# ProPrj_DevBoard_2026-04-14.net
KiCad netlist of a schematic drawn in EasyEDA Pro
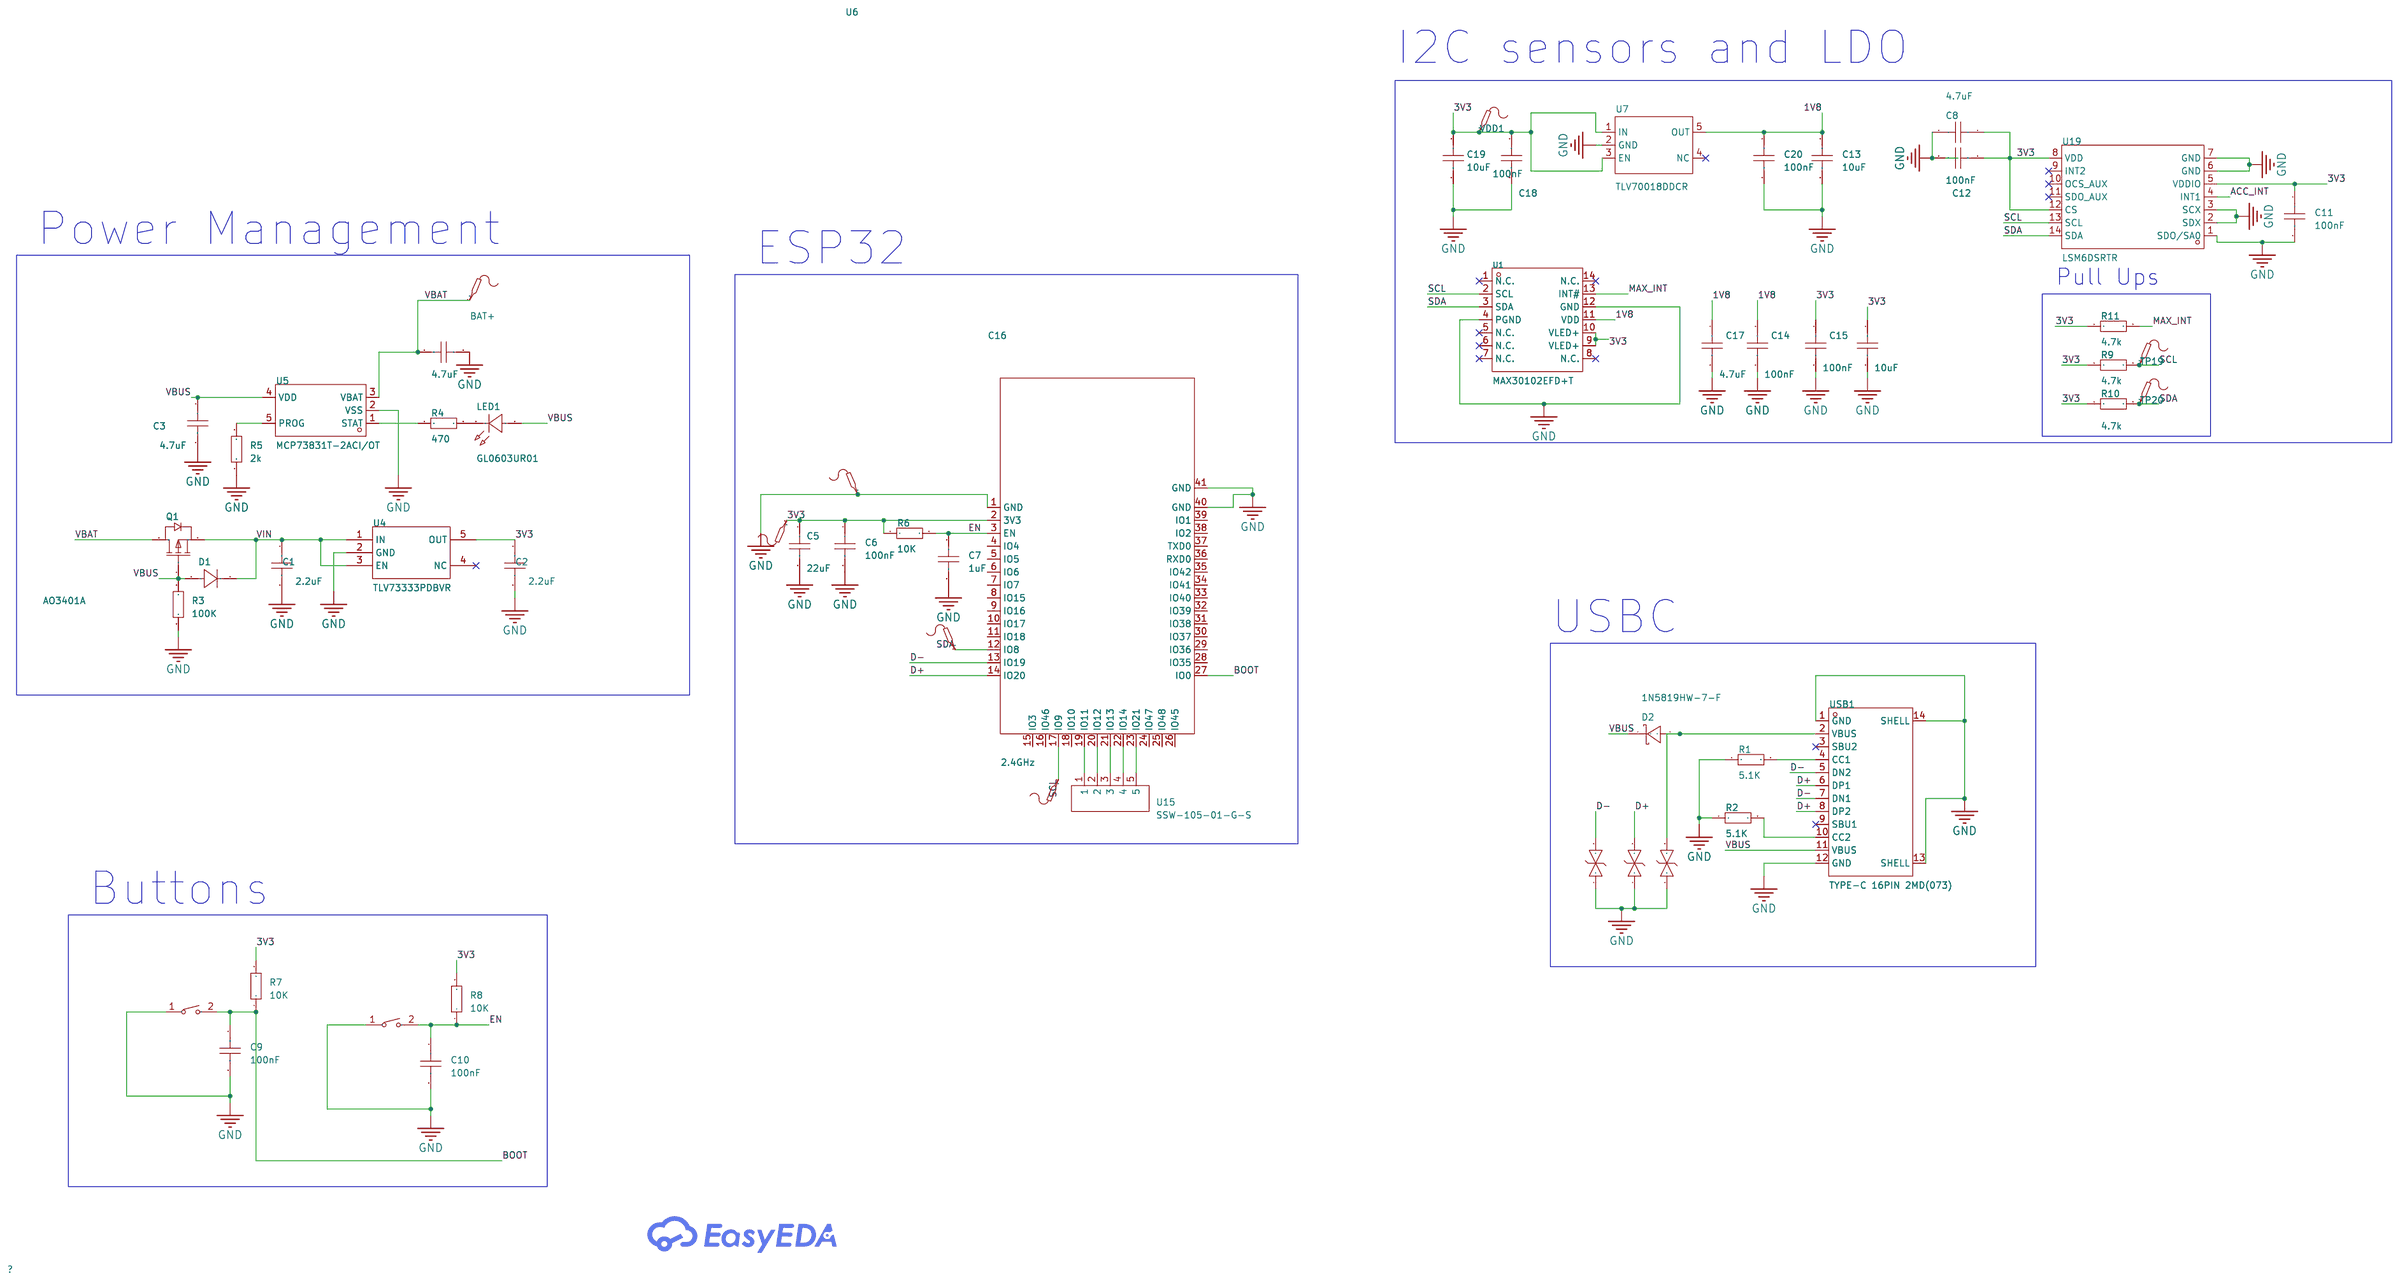
[diagram p0: schematic sheet]

(export (version "E")
  (design (tool "Eeschema 10.0.6"))
  (components
    (comp (ref "BAT+")
      (value "~")
      (footprint "easyedapro:Test-Point-0.5mm")
      (description "Test Point 测试点")
      (libsource (lib "easyedapro") (part "Test-Point"))
    )
    (comp (ref "BAT+1")
      (value "~")
      (footprint "easyedapro:Test-Point-0.5mm")
      (description "Test Point 测试点")
      (libsource (lib "easyedapro") (part "Test-Point"))
    )
    (comp (ref "BAT+2")
      (value "~")
      (footprint "easyedapro:Test-Point-0.5mm")
      (description "Test Point 测试点")
      (libsource (lib "easyedapro") (part "Test-Point"))
    )
    (comp (ref "BAT+3")
      (value "~")
      (footprint "easyedapro:Test-Point-0.5mm")
      (description "Test Point 测试点")
      (libsource (lib "easyedapro") (part "Test-Point"))
    )
    (comp (ref "BAT+4")
      (value "~")
      (footprint "easyedapro:Test-Point-0.5mm")
      (description "Test Point 测试点")
      (libsource (lib "easyedapro") (part "Test-Point"))
    )
    (comp (ref "C1")
      (value "2.2uF")
      (footprint "easyedapro:C0603")
      (libsource (lib "easyedapro") (part "CAP"))
    )
    (comp (ref "C2")
      (value "2.2uF")
      (footprint "easyedapro:C0603")
      (libsource (lib "easyedapro") (part "CAP"))
    )
    (comp (ref "C3")
      (value "4.7uF")
      (footprint "easyedapro:C0603")
      (libsource (lib "easyedapro") (part "CAP"))
    )
    (comp (ref "C4")
      (value "4.7uF")
      (footprint "easyedapro:C0603")
      (libsource (lib "easyedapro") (part "CAP"))
    )
    (comp (ref "C5")
      (value "22uF")
      (footprint "easyedapro:C0603")
      (libsource (lib "easyedapro") (part "CAP"))
    )
    (comp (ref "C6")
      (value "100nF")
      (footprint "easyedapro:C0603")
      (libsource (lib "easyedapro") (part "CAP"))
    )
    (comp (ref "C7") (value "1uF") (footprint "easyedapro:C0603") (libsource (lib "easyedapro") (part "CAP")))
    (comp (ref "C8")
      (value "4.7uF")
      (footprint "easyedapro:C0603")
      (libsource (lib "easyedapro") (part "CAP"))
    )
    (comp (ref "C9")
      (value "100nF")
      (footprint "easyedapro:C0603")
      (libsource (lib "easyedapro") (part "CAP"))
    )
    (comp (ref "C10")
      (value "100nF")
      (footprint "easyedapro:C0603")
      (libsource (lib "easyedapro") (part "CAP"))
    )
    (comp (ref "C11")
      (value "100nF")
      (footprint "easyedapro:C0603")
      (libsource (lib "easyedapro") (part "CAP"))
    )
    (comp (ref "C12")
      (value "100nF")
      (footprint "easyedapro:C0603")
      (libsource (lib "easyedapro") (part "CAP"))
    )
    (comp (ref "C13")
      (value "10uF")
      (footprint "easyedapro:C0603")
      (libsource (lib "easyedapro") (part "CAP"))
    )
    (comp (ref "C14")
      (value "100nF")
      (footprint "easyedapro:C0603")
      (libsource (lib "easyedapro") (part "CAP"))
    )
    (comp (ref "C15")
      (value "100nF")
      (footprint "easyedapro:C0603")
      (libsource (lib "easyedapro") (part "CAP"))
    )
    (comp (ref "C16")
      (value "10uF")
      (footprint "easyedapro:C0603")
      (libsource (lib "easyedapro") (part "CAP"))
    )
    (comp (ref "C17")
      (value "4.7uF")
      (footprint "easyedapro:C0603")
      (libsource (lib "easyedapro") (part "CAP"))
    )
    (comp (ref "C18")
      (value "100nF")
      (footprint "easyedapro:C0603")
      (libsource (lib "easyedapro") (part "CAP"))
    )
    (comp (ref "C19")
      (value "10uF")
      (footprint "easyedapro:C0603")
      (libsource (lib "easyedapro") (part "CAP"))
    )
    (comp (ref "C20")
      (value "100nF")
      (footprint "easyedapro:C0603")
      (libsource (lib "easyedapro") (part "CAP"))
    )
    (comp (ref "D1")
      (value "~")
      (footprint "easyedapro:SMA_L4.4-W2.8-LS5.4-RD")
      (libsource (lib "easyedapro") (part "D_1N4007"))
    )
    (comp (ref "D2")
      (value "1N5819HW-7-F")
      (footprint "easyedapro:SOD-123_L2.7-W1.6-LS3.7-RD")
      (fields (field (name "Manufacturer") "DIODES(美台)"))
      (libsource (lib "easyedapro") (part "1N5819HW-7-F"))
    )
    (comp (ref "LED1")
      (value "GL0603UR01")
      (footprint "easyedapro:LED0603-FD")
      (fields (field (name "Manufacturer") "Guiguang light(桂光光电)"))
      (libsource (lib "easyedapro") (part "GL0603UR01"))
    )
    (comp (ref "Q1")
      (value "AO3401A")
      (footprint "easyedapro:SOT-23_L2.9-W1.3-P1.90-LS2.4-BR")
      (fields (field (name "Manufacturer") "AOS"))
      (libsource (lib "easyedapro") (part "AO3401A"))
    )
    (comp (ref "R1")
      (value "5.1K")
      (footprint "easyedapro:R0603")
      (libsource (lib "easyedapro") (part "Res"))
    )
    (comp (ref "R2")
      (value "5.1K")
      (footprint "easyedapro:R0603")
      (libsource (lib "easyedapro") (part "Res"))
    )
    (comp (ref "R3")
      (value "100K")
      (footprint "easyedapro:R0603")
      (libsource (lib "easyedapro") (part "Res"))
    )
    (comp (ref "R4") (value "470") (footprint "easyedapro:R0603") (libsource (lib "easyedapro") (part "Res")))
    (comp (ref "R5") (value "2k") (footprint "easyedapro:R0603") (libsource (lib "easyedapro") (part "Res")))
    (comp (ref "R6") (value "10K") (footprint "easyedapro:R0603") (libsource (lib "easyedapro") (part "Res")))
    (comp (ref "R7") (value "10K") (footprint "easyedapro:R0603") (libsource (lib "easyedapro") (part "Res")))
    (comp (ref "R8") (value "10K") (footprint "easyedapro:R0603") (libsource (lib "easyedapro") (part "Res")))
    (comp (ref "R9")
      (value "4.7k")
      (footprint "easyedapro:R0603")
      (libsource (lib "easyedapro") (part "Res"))
    )
    (comp (ref "R10")
      (value "4.7k")
      (footprint "easyedapro:R0603")
      (libsource (lib "easyedapro") (part "Res"))
    )
    (comp (ref "R11")
      (value "4.7k")
      (footprint "easyedapro:R0603")
      (libsource (lib "easyedapro") (part "Res"))
    )
    (comp (ref "TP19")
      (value "~")
      (footprint "easyedapro:Test-Point-0.5mm")
      (description "Test Point 测试点")
      (libsource (lib "easyedapro") (part "Test-Point"))
    )
    (comp (ref "TP20")
      (value "~")
      (footprint "easyedapro:Test-Point-0.5mm")
      (description "Test Point 测试点")
      (libsource (lib "easyedapro") (part "Test-Point"))
    )
    (comp (ref "U1")
      (value "MAX30102EFD+T")
      (footprint "easyedapro:OESIP-14_L5.6-W3.3-P0.80-TL")
      (description "Operating Temperature:-40°C~+85°C Operating Temperature:-40°C~+85°C")
      (fields (field (name "Manufacturer") "ADI(亚德诺)/MAXIM(美信)"))
      (libsource (lib "easyedapro") (part "MAX30102EFD+T_C6454833"))
    )
    (comp (ref "U4")
      (value "TLV73333PDBVR")
      (footprint "easyedapro:SOT-23-5_L3.0-W1.7-P0.95-LS2.8-BR")
      (fields (field (name "Manufacturer") "TI(德州仪器)"))
      (libsource (lib "easyedapro") (part "TLV73333PDBVR"))
    )
    (comp (ref "U5")
      (value "MCP73831T-2ACI/OT")
      (footprint "easyedapro:SOT-23-5_L3.0-W1.7-P0.95-LS2.8-BL")
      (fields (field (name "Manufacturer") "MICROCHIP(美国微芯)"))
      (libsource (lib "easyedapro") (part "MCP73831T-2ACI/OT"))
    )
    (comp (ref "U6")
      (value "2.4GHz")
      (footprint "easyedapro:WIRELM-SMD_ESP32-S3-WROOM-1")
      (fields
        (field (name "Manufacturer Part") "ESP32-S3-WROOM-1-N16R8")
        (field (name "Manufacturer") "ESPRESSIF(乐鑫)")
      )
      (libsource (lib "easyedapro") (part "ESP32-S3-WROOM-1(N16R8)"))
    )
    (comp (ref "U7")
      (value "TLV70018DDCR")
      (footprint "easyedapro:SOT-23-5_L3.0-W1.7-P0.95-LS2.8-BR")
      (fields (field (name "Manufacturer") "TI(德州仪器)"))
      (libsource (lib "easyedapro") (part "TLV70018DDCR"))
    )
    (comp (ref "U8")
      (value "GT-TC060A-H025-L1")
      (footprint "easyedapro:SW-SMD_L6.1-W3.5-LS8.0")
      (fields (field (name "Manufacturer") "G-Switch(品赞)"))
      (libsource (lib "easyedapro") (part "GT-TC060A-H025-L1"))
    )
    (comp (ref "U9")
      (value "GT-TC060A-H025-L1")
      (footprint "easyedapro:SW-SMD_L6.1-W3.5-LS8.0")
      (fields (field (name "Manufacturer") "G-Switch(品赞)"))
      (libsource (lib "easyedapro") (part "GT-TC060A-H025-L1"))
    )
    (comp (ref "U15")
      (value "SSW-105-01-G-S")
      (footprint "easyedapro:HDR-TH_5P-P2.54_SSW-105-01-S-P")
      (fields (field (name "Manufacturer") "SAMTEC"))
      (libsource (lib "easyedapro") (part "SSW-105-01-G-S"))
    )
    (comp (ref "U16")
      (value "LESD5D5.0CT1G")
      (footprint "easyedapro:SOD-523_L1.2-W0.8-LS1.6-BI")
      (fields (field (name "Manufacturer") "KUU"))
      (libsource (lib "easyedapro") (part "LESD5D5.0CT1G_C7433850"))
    )
    (comp (ref "U17")
      (value "LESD5D5.0CT1G")
      (footprint "easyedapro:SOD-523_L1.2-W0.8-LS1.6-BI")
      (fields (field (name "Manufacturer") "KUU"))
      (libsource (lib "easyedapro") (part "LESD5D5.0CT1G_C7433850"))
    )
    (comp (ref "U18")
      (value "LESD5D5.0CT1G")
      (footprint "easyedapro:SOD-523_L1.2-W0.8-LS1.6-BI")
      (fields (field (name "Manufacturer") "KUU"))
      (libsource (lib "easyedapro") (part "LESD5D5.0CT1G_C7433850"))
    )
    (comp (ref "U19")
      (value "LSM6DSRTR")
      (footprint "easyedapro:LGA-14_L3.0-W2.5-P0.50-BR")
      (fields (field (name "Manufacturer") "ST(意法半导体)"))
      (libsource (lib "easyedapro") (part "LSM6DSRTR"))
    )
    (comp (ref "USB1")
      (value "TYPE-C 16PIN 2MD(073)")
      (footprint "easyedapro:USB-C-SMD_TYPE-C-6PIN-2MD-073")
      (fields (field (name "Manufacturer") "SHOU HAN(首韩)"))
      (libsource (lib "easyedapro") (part "TYPE-C 16PIN 2MD(073)"))
    )
    (comp (ref "VDD1")
      (value "~")
      (footprint "easyedapro:Test-Point-0.5mm")
      (description "Test Point 测试点")
      (libsource (lib "easyedapro") (part "Test-Point"))
    )
  )
  (nets
    (net (code "1") (name "/1V8") (class "Default")
      (node (ref "C13") (pin "1") (pinfunction "1_1") (pintype "input"))
      (node (ref "C14") (pin "1") (pinfunction "1_1") (pintype "input"))
      (node (ref "C17") (pin "1") (pinfunction "1_1") (pintype "input"))
      (node (ref "C20") (pin "1") (pinfunction "1_1") (pintype "input"))
      (node (ref "U1") (pin "11") (pinfunction "VDD_11") (pintype "input"))
      (node (ref "U7") (pin "5") (pinfunction "OUT_5") (pintype "unspecified"))
    )
    (net (code "2") (name "/3V3") (class "Default")
      (node (ref "BAT+3") (pin "1") (pinfunction "1_1") (pintype "unspecified"))
      (node (ref "C11") (pin "1") (pinfunction "1_1") (pintype "input"))
      (node (ref "C12") (pin "1") (pinfunction "1_1") (pintype "input"))
      (node (ref "C15") (pin "1") (pinfunction "1_1") (pintype "input"))
      (node (ref "C16") (pin "1") (pinfunction "1_1") (pintype "input"))
      (node (ref "C18") (pin "1") (pinfunction "1_1") (pintype "input"))
      (node (ref "C19") (pin "1") (pinfunction "1_1") (pintype "input"))
      (node (ref "C2") (pin "1") (pinfunction "1_1") (pintype "input"))
      (node (ref "C5") (pin "1") (pinfunction "1_1") (pintype "input"))
      (node (ref "C6") (pin "1") (pinfunction "1_1") (pintype "input"))
      (node (ref "C8") (pin "1") (pinfunction "1_1") (pintype "input"))
      (node (ref "R10") (pin "1") (pinfunction "1_1") (pintype "input"))
      (node (ref "R11") (pin "1") (pinfunction "1_1") (pintype "input"))
      (node (ref "R6") (pin "1") (pinfunction "1_1") (pintype "input"))
      (node (ref "R7") (pin "2") (pinfunction "2_2") (pintype "input"))
      (node (ref "R8") (pin "2") (pinfunction "2_2") (pintype "input"))
      (node (ref "R9") (pin "1") (pinfunction "1_1") (pintype "input"))
      (node (ref "U1") (pin "10") (pinfunction "VLED+_10") (pintype "input"))
      (node (ref "U1") (pin "9") (pinfunction "VLED+_9") (pintype "input"))
      (node (ref "U19") (pin "12") (pinfunction "CS_12") (pintype "unspecified"))
      (node (ref "U19") (pin "5") (pinfunction "VDDIO_5") (pintype "unspecified"))
      (node (ref "U19") (pin "8") (pinfunction "VDD_8") (pintype "unspecified"))
      (node (ref "U4") (pin "5") (pinfunction "OUT_5") (pintype "unspecified"))
      (node (ref "U6") (pin "2") (pinfunction "3V3_2") (pintype "unspecified"))
      (node (ref "U7") (pin "1") (pinfunction "IN_1") (pintype "unspecified"))
      (node (ref "U7") (pin "3") (pinfunction "EN_3") (pintype "unspecified"))
      (node (ref "VDD1") (pin "1") (pinfunction "1_1") (pintype "unspecified"))
    )
    (net (code "3") (name "/ACC_INT") (class "Default")
      (node (ref "U19") (pin "4") (pinfunction "INT1_4") (pintype "unspecified"))
    )
    (net (code "4") (name "/BOOT") (class "Default")
      (node (ref "C9") (pin "1") (pinfunction "1_1") (pintype "input"))
      (node (ref "R7") (pin "1") (pinfunction "1_1") (pintype "input"))
      (node (ref "U6") (pin "27") (pinfunction "IO0_27") (pintype "unspecified"))
      (node (ref "U8") (pin "2") (pinfunction "2_2") (pintype "unspecified"))
    )
    (net (code "5") (name "/D+") (class "Default")
      (node (ref "U17") (pin "2") (pinfunction "2_2") (pintype "unspecified"))
      (node (ref "U6") (pin "14") (pinfunction "IO20_14") (pintype "unspecified"))
      (node (ref "USB1") (pin "6") (pinfunction "DP1_6") (pintype "unspecified"))
      (node (ref "USB1") (pin "8") (pinfunction "DP2_8") (pintype "unspecified"))
    )
    (net (code "6") (name "/D-") (class "Default")
      (node (ref "U16") (pin "2") (pinfunction "2_2") (pintype "unspecified"))
      (node (ref "U6") (pin "13") (pinfunction "IO19_13") (pintype "unspecified"))
      (node (ref "USB1") (pin "5") (pinfunction "DN2_5") (pintype "unspecified"))
      (node (ref "USB1") (pin "7") (pinfunction "DN1_7") (pintype "unspecified"))
    )
    (net (code "7") (name "/EN") (class "Default")
      (node (ref "C10") (pin "1") (pinfunction "1_1") (pintype "input"))
      (node (ref "C7") (pin "1") (pinfunction "1_1") (pintype "input"))
      (node (ref "R6") (pin "2") (pinfunction "2_2") (pintype "input"))
      (node (ref "R8") (pin "1") (pinfunction "1_1") (pintype "input"))
      (node (ref "U6") (pin "3") (pinfunction "EN_3") (pintype "unspecified"))
      (node (ref "U9") (pin "2") (pinfunction "2_2") (pintype "unspecified"))
    )
    (net (code "8") (name "/MAX_INT") (class "Default")
      (node (ref "R11") (pin "2") (pinfunction "2_2") (pintype "input"))
      (node (ref "U1") (pin "13") (pinfunction "INT#_13") (pintype "input"))
    )
    (net (code "9") (name "/SCL") (class "Default")
      (node (ref "BAT+1") (pin "1") (pinfunction "1_1") (pintype "unspecified"))
      (node (ref "R9") (pin "2") (pinfunction "2_2") (pintype "input"))
      (node (ref "TP19") (pin "1") (pinfunction "1_1") (pintype "unspecified"))
      (node (ref "U1") (pin "2") (pinfunction "SCL_2") (pintype "input"))
      (node (ref "U19") (pin "13") (pinfunction "SCL_13") (pintype "unspecified"))
      (node (ref "U6") (pin "17") (pinfunction "IO9_17") (pintype "unspecified"))
    )
    (net (code "10") (name "/SDA") (class "Default")
      (node (ref "BAT+2") (pin "1") (pinfunction "1_1") (pintype "unspecified"))
      (node (ref "R10") (pin "2") (pinfunction "2_2") (pintype "input"))
      (node (ref "TP20") (pin "1") (pinfunction "1_1") (pintype "unspecified"))
      (node (ref "U1") (pin "3") (pinfunction "SDA_3") (pintype "input"))
      (node (ref "U19") (pin "14") (pinfunction "SDA_14") (pintype "unspecified"))
      (node (ref "U6") (pin "12") (pinfunction "IO8_12") (pintype "unspecified"))
    )
    (net (code "11") (name "/VBAT") (class "Default")
      (node (ref "BAT+") (pin "1") (pinfunction "1_1") (pintype "unspecified"))
      (node (ref "C4") (pin "1") (pinfunction "1_1") (pintype "input"))
      (node (ref "Q1") (pin "3") (pinfunction "D_3") (pintype "unspecified"))
      (node (ref "U5") (pin "3") (pinfunction "VBAT_3") (pintype "unspecified"))
    )
    (net (code "12") (name "/VBUS") (class "Default")
      (node (ref "C3") (pin "1") (pinfunction "1_1") (pintype "input"))
      (node (ref "D1") (pin "2") (pinfunction "A_2") (pintype "input"))
      (node (ref "D2") (pin "1") (pinfunction "K_1") (pintype "unspecified"))
      (node (ref "LED1") (pin "1") (pinfunction "A_1") (pintype "unspecified"))
      (node (ref "Q1") (pin "1") (pinfunction "G_1") (pintype "unspecified"))
      (node (ref "R3") (pin "2") (pinfunction "2_2") (pintype "input"))
      (node (ref "U5") (pin "4") (pinfunction "VDD_4") (pintype "unspecified"))
      (node (ref "USB1") (pin "11") (pinfunction "VBUS_11") (pintype "unspecified"))
    )
    (net (code "13") (name "/VIN") (class "Default")
      (node (ref "C1") (pin "1") (pinfunction "1_1") (pintype "input"))
      (node (ref "D1") (pin "1") (pinfunction "K_1") (pintype "input"))
      (node (ref "Q1") (pin "2") (pinfunction "S_2") (pintype "unspecified"))
      (node (ref "U4") (pin "1") (pinfunction "IN_1") (pintype "unspecified"))
      (node (ref "U4") (pin "3") (pinfunction "EN_3") (pintype "unspecified"))
    )
    (net (code "14") (name "GND") (class "Default")
      (node (ref "BAT+4") (pin "1") (pinfunction "1_1") (pintype "unspecified"))
      (node (ref "C1") (pin "2") (pinfunction "2_2") (pintype "input"))
      (node (ref "C10") (pin "2") (pinfunction "2_2") (pintype "input"))
      (node (ref "C11") (pin "2") (pinfunction "2_2") (pintype "input"))
      (node (ref "C12") (pin "2") (pinfunction "2_2") (pintype "input"))
      (node (ref "C13") (pin "2") (pinfunction "2_2") (pintype "input"))
      (node (ref "C14") (pin "2") (pinfunction "2_2") (pintype "input"))
      (node (ref "C15") (pin "2") (pinfunction "2_2") (pintype "input"))
      (node (ref "C16") (pin "2") (pinfunction "2_2") (pintype "input"))
      (node (ref "C17") (pin "2") (pinfunction "2_2") (pintype "input"))
      (node (ref "C18") (pin "2") (pinfunction "2_2") (pintype "input"))
      (node (ref "C19") (pin "2") (pinfunction "2_2") (pintype "input"))
      (node (ref "C2") (pin "2") (pinfunction "2_2") (pintype "input"))
      (node (ref "C20") (pin "2") (pinfunction "2_2") (pintype "input"))
      (node (ref "C3") (pin "2") (pinfunction "2_2") (pintype "input"))
      (node (ref "C4") (pin "2") (pinfunction "2_2") (pintype "input"))
      (node (ref "C5") (pin "2") (pinfunction "2_2") (pintype "input"))
      (node (ref "C6") (pin "2") (pinfunction "2_2") (pintype "input"))
      (node (ref "C7") (pin "2") (pinfunction "2_2") (pintype "input"))
      (node (ref "C8") (pin "2") (pinfunction "2_2") (pintype "input"))
      (node (ref "C9") (pin "2") (pinfunction "2_2") (pintype "input"))
      (node (ref "R1") (pin "1") (pinfunction "1_1") (pintype "input"))
      (node (ref "R2") (pin "1") (pinfunction "1_1") (pintype "input"))
      (node (ref "R3") (pin "1") (pinfunction "1_1") (pintype "input"))
      (node (ref "R5") (pin "1") (pinfunction "1_1") (pintype "input"))
      (node (ref "U1") (pin "12") (pinfunction "GND_12") (pintype "input"))
      (node (ref "U1") (pin "4") (pinfunction "PGND_4") (pintype "input"))
      (node (ref "U16") (pin "1") (pinfunction "1_1") (pintype "unspecified"))
      (node (ref "U17") (pin "1") (pinfunction "1_1") (pintype "unspecified"))
      (node (ref "U18") (pin "1") (pinfunction "1_1") (pintype "unspecified"))
      (node (ref "U19") (pin "1") (pinfunction "SDO/SA0_1") (pintype "unspecified"))
      (node (ref "U19") (pin "2") (pinfunction "SDX_2") (pintype "unspecified"))
      (node (ref "U19") (pin "3") (pinfunction "SCX_3") (pintype "unspecified"))
      (node (ref "U19") (pin "6") (pinfunction "GND_6") (pintype "unspecified"))
      (node (ref "U19") (pin "7") (pinfunction "GND_7") (pintype "unspecified"))
      (node (ref "U4") (pin "2") (pinfunction "GND_2") (pintype "unspecified"))
      (node (ref "U5") (pin "2") (pinfunction "VSS_2") (pintype "unspecified"))
      (node (ref "U6") (pin "1") (pinfunction "GND_1") (pintype "unspecified"))
      (node (ref "U6") (pin "40") (pinfunction "GND_40") (pintype "unspecified"))
      (node (ref "U6") (pin "41") (pinfunction "GND_41") (pintype "unspecified"))
      (node (ref "U7") (pin "2") (pinfunction "GND_2") (pintype "unspecified"))
      (node (ref "U8") (pin "1") (pinfunction "1_1") (pintype "unspecified"))
      (node (ref "U9") (pin "1") (pinfunction "1_1") (pintype "unspecified"))
      (node (ref "USB1") (pin "1") (pinfunction "GND_1") (pintype "unspecified"))
      (node (ref "USB1") (pin "12") (pinfunction "GND_12") (pintype "unspecified"))
      (node (ref "USB1") (pin "13") (pinfunction "SHELL_13") (pintype "unspecified"))
      (node (ref "USB1") (pin "14") (pinfunction "SHELL_14") (pintype "unspecified"))
    )
    (net (code "15") (name "Net-(D2-A)") (class "Default")
      (node (ref "D2") (pin "2") (pinfunction "A_2") (pintype "unspecified"))
      (node (ref "U18") (pin "2") (pinfunction "2_2") (pintype "unspecified"))
      (node (ref "USB1") (pin "2") (pinfunction "VBUS_2") (pintype "unspecified"))
    )
    (net (code "16") (name "Net-(LED1-C)") (class "Default")
      (node (ref "LED1") (pin "2") (pinfunction "C_2") (pintype "unspecified"))
      (node (ref "R4") (pin "2") (pinfunction "2_2") (pintype "input"))
    )
    (net (code "17") (name "Net-(U5-PROG)") (class "Default")
      (node (ref "R5") (pin "2") (pinfunction "2_2") (pintype "input"))
      (node (ref "U5") (pin "5") (pinfunction "PROG_5") (pintype "unspecified"))
    )
    (net (code "18") (name "Net-(U5-STAT)") (class "Default")
      (node (ref "R4") (pin "1") (pinfunction "1_1") (pintype "input"))
      (node (ref "U5") (pin "1") (pinfunction "STAT_1") (pintype "unspecified"))
    )
    (net (code "19") (name "Net-(U6-IO11)") (class "Default")
      (node (ref "U15") (pin "1") (pinfunction "1_1") (pintype "unspecified"))
      (node (ref "U6") (pin "19") (pinfunction "IO11_19") (pintype "unspecified"))
    )
    (net (code "20") (name "Net-(U6-IO12)") (class "Default")
      (node (ref "U15") (pin "2") (pinfunction "2_2") (pintype "unspecified"))
      (node (ref "U6") (pin "20") (pinfunction "IO12_20") (pintype "unspecified"))
    )
    (net (code "21") (name "Net-(U6-IO13)") (class "Default")
      (node (ref "U15") (pin "3") (pinfunction "3_3") (pintype "unspecified"))
      (node (ref "U6") (pin "21") (pinfunction "IO13_21") (pintype "unspecified"))
    )
    (net (code "22") (name "Net-(U6-IO14)") (class "Default")
      (node (ref "U15") (pin "4") (pinfunction "4_4") (pintype "unspecified"))
      (node (ref "U6") (pin "22") (pinfunction "IO14_22") (pintype "unspecified"))
    )
    (net (code "23") (name "Net-(U6-IO21)") (class "Default")
      (node (ref "U15") (pin "5") (pinfunction "5_5") (pintype "unspecified"))
      (node (ref "U6") (pin "23") (pinfunction "IO21_23") (pintype "unspecified"))
    )
    (net (code "24") (name "Net-(USB1-CC1)") (class "Default")
      (node (ref "R1") (pin "2") (pinfunction "2_2") (pintype "input"))
      (node (ref "USB1") (pin "4") (pinfunction "CC1_4") (pintype "unspecified"))
    )
    (net (code "25") (name "Net-(USB1-CC2)") (class "Default")
      (node (ref "R2") (pin "2") (pinfunction "2_2") (pintype "input"))
      (node (ref "USB1") (pin "10") (pinfunction "CC2_10") (pintype "unspecified"))
    )
    (net (code "26") (name "unconnected-(U1-N.C.-Pad1)") (class "Default")
      (node (ref "U1") (pin "1") (pinfunction "N.C._1") (pintype "input+no_connect"))
    )
    (net (code "27") (name "unconnected-(U1-N.C.-Pad5)") (class "Default")
      (node (ref "U1") (pin "5") (pinfunction "N.C._5") (pintype "input+no_connect"))
    )
    (net (code "28") (name "unconnected-(U1-N.C.-Pad6)") (class "Default")
      (node (ref "U1") (pin "6") (pinfunction "N.C._6") (pintype "input+no_connect"))
    )
    (net (code "29") (name "unconnected-(U1-N.C.-Pad7)") (class "Default")
      (node (ref "U1") (pin "7") (pinfunction "N.C._7") (pintype "input+no_connect"))
    )
    (net (code "30") (name "unconnected-(U1-N.C.-Pad8)") (class "Default")
      (node (ref "U1") (pin "8") (pinfunction "N.C._8") (pintype "input+no_connect"))
    )
    (net (code "31") (name "unconnected-(U1-N.C.-Pad14)") (class "Default")
      (node (ref "U1") (pin "14") (pinfunction "N.C._14") (pintype "input+no_connect"))
    )
    (net (code "32") (name "unconnected-(U4-NC-Pad4)") (class "Default")
      (node (ref "U4") (pin "4") (pinfunction "NC_4") (pintype "unspecified+no_connect"))
    )
    (net (code "33") (name "unconnected-(U6-IO1-Pad39)") (class "Default")
      (node (ref "U6") (pin "39") (pinfunction "IO1_39") (pintype "unspecified"))
    )
    (net (code "34") (name "unconnected-(U6-IO2-Pad38)") (class "Default")
      (node (ref "U6") (pin "38") (pinfunction "IO2_38") (pintype "unspecified"))
    )
    (net (code "35") (name "unconnected-(U6-IO3-Pad15)") (class "Default")
      (node (ref "U6") (pin "15") (pinfunction "IO3_15") (pintype "unspecified"))
    )
    (net (code "36") (name "unconnected-(U6-IO4-Pad4)") (class "Default")
      (node (ref "U6") (pin "4") (pinfunction "IO4_4") (pintype "unspecified"))
    )
    (net (code "37") (name "unconnected-(U6-IO5-Pad5)") (class "Default")
      (node (ref "U6") (pin "5") (pinfunction "IO5_5") (pintype "unspecified"))
    )
    (net (code "38") (name "unconnected-(U6-IO6-Pad6)") (class "Default")
      (node (ref "U6") (pin "6") (pinfunction "IO6_6") (pintype "unspecified"))
    )
    (net (code "39") (name "unconnected-(U6-IO7-Pad7)") (class "Default")
      (node (ref "U6") (pin "7") (pinfunction "IO7_7") (pintype "unspecified"))
    )
    (net (code "40") (name "unconnected-(U6-IO10-Pad18)") (class "Default")
      (node (ref "U6") (pin "18") (pinfunction "IO10_18") (pintype "unspecified"))
    )
    (net (code "41") (name "unconnected-(U6-IO15-Pad8)") (class "Default")
      (node (ref "U6") (pin "8") (pinfunction "IO15_8") (pintype "unspecified"))
    )
    (net (code "42") (name "unconnected-(U6-IO16-Pad9)") (class "Default")
      (node (ref "U6") (pin "9") (pinfunction "IO16_9") (pintype "unspecified"))
    )
    (net (code "43") (name "unconnected-(U6-IO17-Pad10)") (class "Default")
      (node (ref "U6") (pin "10") (pinfunction "IO17_10") (pintype "unspecified"))
    )
    (net (code "44") (name "unconnected-(U6-IO18-Pad11)") (class "Default")
      (node (ref "U6") (pin "11") (pinfunction "IO18_11") (pintype "unspecified"))
    )
    (net (code "45") (name "unconnected-(U6-IO35-Pad28)") (class "Default")
      (node (ref "U6") (pin "28") (pinfunction "IO35_28") (pintype "unspecified"))
    )
    (net (code "46") (name "unconnected-(U6-IO36-Pad29)") (class "Default")
      (node (ref "U6") (pin "29") (pinfunction "IO36_29") (pintype "unspecified"))
    )
    (net (code "47") (name "unconnected-(U6-IO37-Pad30)") (class "Default")
      (node (ref "U6") (pin "30") (pinfunction "IO37_30") (pintype "unspecified"))
    )
    (net (code "48") (name "unconnected-(U6-IO38-Pad31)") (class "Default")
      (node (ref "U6") (pin "31") (pinfunction "IO38_31") (pintype "unspecified"))
    )
    (net (code "49") (name "unconnected-(U6-IO39-Pad32)") (class "Default")
      (node (ref "U6") (pin "32") (pinfunction "IO39_32") (pintype "unspecified"))
    )
    (net (code "50") (name "unconnected-(U6-IO40-Pad33)") (class "Default")
      (node (ref "U6") (pin "33") (pinfunction "IO40_33") (pintype "unspecified"))
    )
    (net (code "51") (name "unconnected-(U6-IO41-Pad34)") (class "Default")
      (node (ref "U6") (pin "34") (pinfunction "IO41_34") (pintype "unspecified"))
    )
    (net (code "52") (name "unconnected-(U6-IO42-Pad35)") (class "Default")
      (node (ref "U6") (pin "35") (pinfunction "IO42_35") (pintype "unspecified"))
    )
    (net (code "53") (name "unconnected-(U6-IO45-Pad26)") (class "Default")
      (node (ref "U6") (pin "26") (pinfunction "IO45_26") (pintype "unspecified"))
    )
    (net (code "54") (name "unconnected-(U6-IO46-Pad16)") (class "Default")
      (node (ref "U6") (pin "16") (pinfunction "IO46_16") (pintype "unspecified"))
    )
    (net (code "55") (name "unconnected-(U6-IO47-Pad24)") (class "Default")
      (node (ref "U6") (pin "24") (pinfunction "IO47_24") (pintype "unspecified"))
    )
    (net (code "56") (name "unconnected-(U6-IO48-Pad25)") (class "Default")
      (node (ref "U6") (pin "25") (pinfunction "IO48_25") (pintype "unspecified"))
    )
    (net (code "57") (name "unconnected-(U6-RXD0-Pad36)") (class "Default")
      (node (ref "U6") (pin "36") (pinfunction "RXD0_36") (pintype "unspecified"))
    )
    (net (code "58") (name "unconnected-(U6-TXD0-Pad37)") (class "Default")
      (node (ref "U6") (pin "37") (pinfunction "TXD0_37") (pintype "unspecified"))
    )
    (net (code "59") (name "unconnected-(U7-NC-Pad4)") (class "Default")
      (node (ref "U7") (pin "4") (pinfunction "NC_4") (pintype "unspecified+no_connect"))
    )
    (net (code "60") (name "unconnected-(U19-INT2-Pad9)") (class "Default")
      (node (ref "U19") (pin "9") (pinfunction "INT2_9") (pintype "unspecified+no_connect"))
    )
    (net (code "61") (name "unconnected-(U19-OCS_AUX-Pad10)") (class "Default")
      (node (ref "U19") (pin "10") (pinfunction "OCS_AUX_10") (pintype "unspecified+no_connect"))
    )
    (net (code "62") (name "unconnected-(U19-SDO_AUX-Pad11)") (class "Default")
      (node (ref "U19") (pin "11") (pinfunction "SDO_AUX_11") (pintype "unspecified+no_connect"))
    )
    (net (code "63") (name "unconnected-(USB1-SBU1-Pad9)") (class "Default")
      (node (ref "USB1") (pin "9") (pinfunction "SBU1_9") (pintype "unspecified+no_connect"))
    )
    (net (code "64") (name "unconnected-(USB1-SBU2-Pad3)") (class "Default")
      (node (ref "USB1") (pin "3") (pinfunction "SBU2_3") (pintype "unspecified+no_connect"))
    )
  )
)
